# Power_Esc.net
KiCad netlist of a schematic drawn in Altium Designer
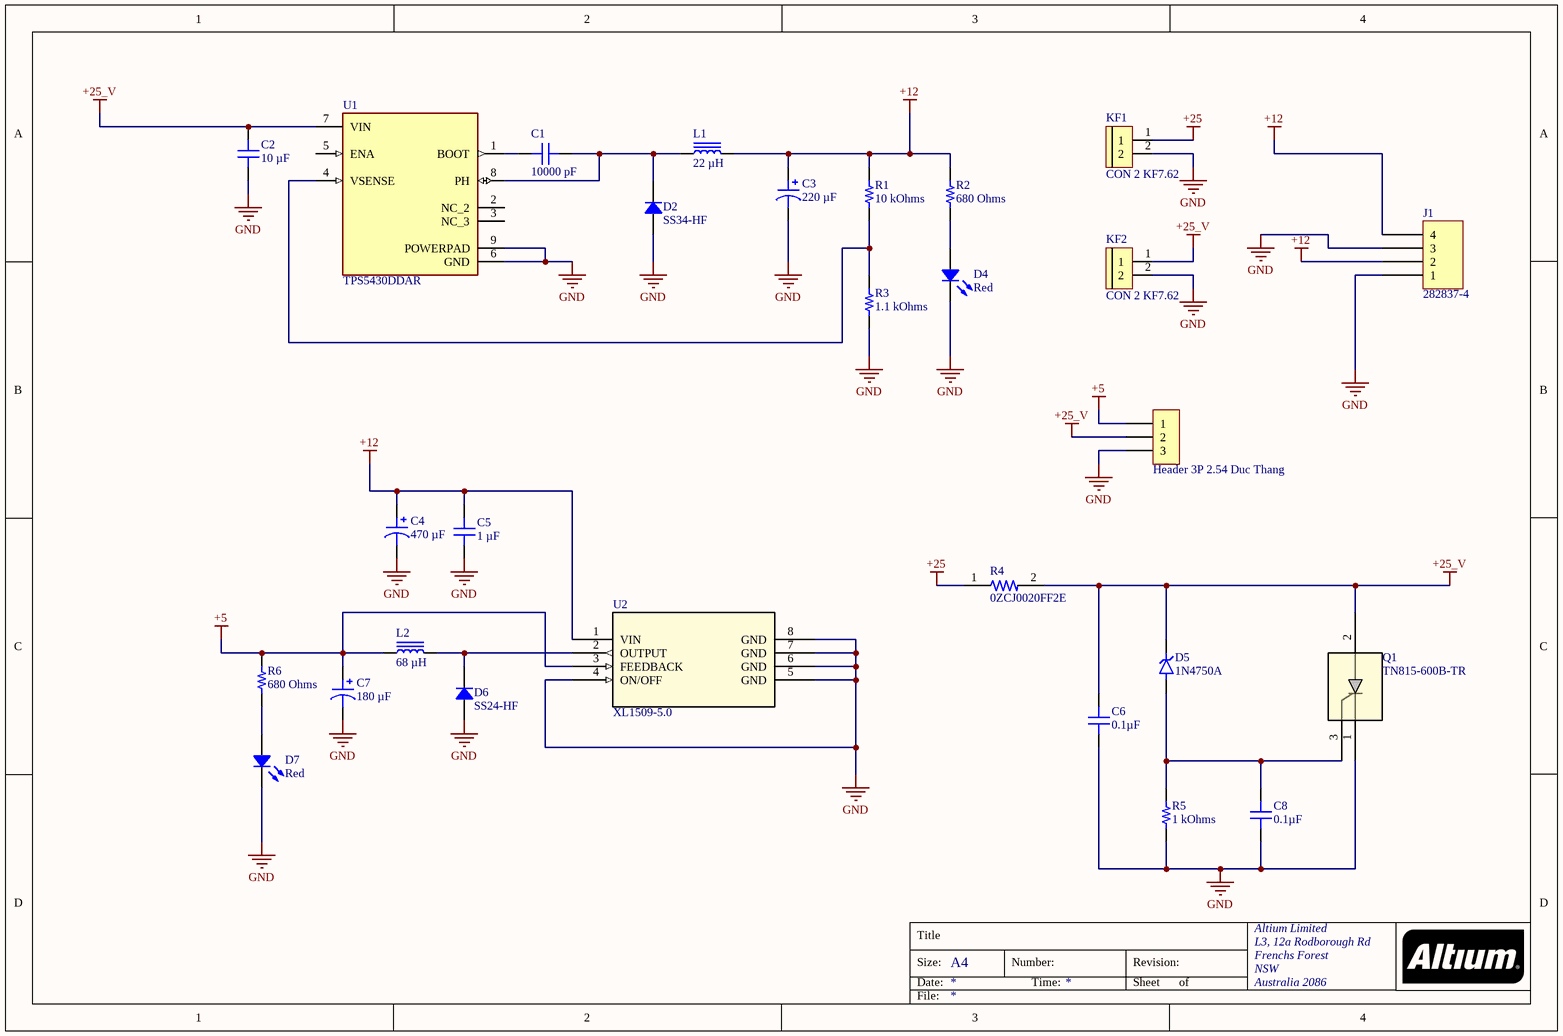
[diagram p0: Power_Esc.SchDoc]

(export (version "E")
  (design (tool "Eeschema 10.0.6"))
  (components
    (comp (ref "C1")
      (value "10000 pF")
      (footprint "CAP 0603_1608")
      (description "CAP CER 0603 10NF 16V X7R 10%")
      (fields (field (name "PART NUMBER") "C0603C103K4REC7867") (field (name "MANUFACTURER") "KEMET"))
      (libsource (lib "Celestial Altium Library - altium_library") (part "Capacitor"))
    )
    (comp (ref "C2")
      (value "10 µF")
      (footprint "CAP 1206_3216 - 0.8MM")
      (description "CAP CER 10UF 50V X5R 1206")
      (fields (field (name "PART NUMBER") "885012108022") (field (name "MANUFACTURER") "Würth Elektronik"))
      (libsource (lib "Celestial Altium Library - altium_library") (part "Capacitor"))
    )
    (comp (ref "C3")
      (value "220 µF")
      (footprint "CAP ALSMD 6.6MM H6.1MM")
      (description "CAP ALUM 220UF 20% 16V SMD")
      (fields
        (field (name "PART NUMBER") "EEE-FT1C221AL")
        (field (name "MANUFACTURER") "Panasonic Electronic Components")
      )
      (libsource (lib "Celestial Altium Library - altium_library") (part "Polarised Capacitor"))
    )
    (comp (ref "C4")
      (value "470 µF")
      (footprint "CAP ALSMD 8.3MM H10.5MM")
      (description "CAP ALUM 470UF 20% 35V SMD")
      (fields
        (field (name "PART NUMBER") "EMZS350ARA471MHA0G")
        (field (name "MANUFACTURER") "United Chemi-Con")
      )
      (libsource (lib "Celestial Altium Library - altium_library") (part "Polarised Capacitor"))
    )
    (comp (ref "C5")
      (value "1 µF")
      (footprint "CAP 0805_2012")
      (description "CAP CER 0805 1UF 16V X7R 5%")
      (fields (field (name "PART NUMBER") "C0805C105J4RECAUTO") (field (name "MANUFACTURER") "KEMET"))
      (libsource (lib "Celestial Altium Library - altium_library") (part "Capacitor"))
    )
    (comp (ref "C6")
      (value "0.1µF")
      (footprint "CAP 0805_2012")
      (description "CAP CER 0.1UF 35V X5R 0805")
      (fields (field (name "PART NUMBER") "0805DD104KAT2A") (field (name "MANUFACTURER") "AVX Corporation"))
      (libsource (lib "Celestial Altium Library - altium_library") (part "Capacitor"))
    )
    (comp (ref "C7")
      (value "180 µF")
      (footprint "CAP ALSMD 6.6MM H8.0MM")
      (description "CAP ALUM 180UF 20% 25V SMD")
      (fields
        (field (name "PART NUMBER") "EEE-FKE181XSP")
        (field (name "MANUFACTURER") "Panasonic Electronic Components")
      )
      (libsource (lib "Celestial Altium Library - altium_library") (part "Polarised Capacitor"))
    )
    (comp (ref "C8")
      (value "0.1µF")
      (footprint "CAP 0805_2012")
      (description "CAP CER 0.1UF 35V X5R 0805")
      (fields (field (name "PART NUMBER") "0805DD104KAT2A") (field (name "MANUFACTURER") "AVX Corporation"))
      (libsource (lib "Celestial Altium Library - altium_library") (part "Capacitor"))
    )
    (comp (ref "D2")
      (value "SS34-HF")
      (footprint "DO214AC SMA")
      (description "DIODE SCHOTTKY 40V 3A DO214AC")
      (fields (field (name "MANUFACTURER") "Comchip Technology"))
      (libsource (lib "Celestial Altium Library - altium_library") (part "Diode"))
    )
    (comp (ref "D4")
      (value "Red")
      (footprint "LED 0805_2012 RED")
      (description "LED RED DIFFUSED 0805 SMD")
      (fields
        (field (name "PART NUMBER") "B1701URO-20D000114U1930")
        (field (name "MANUFACTURER") "Harvatek Corporation")
      )
      (libsource (lib "Celestial Altium Library - altium_library") (part "LED"))
    )
    (comp (ref "D5")
      (value "1N4750A")
      (footprint "DIOAD1060W70L435D230")
      (description "1N4750 Series 1 W 27 V 5 uA Through Hole Zener Diode - DO-41")
      (fields (field (name "MF") "Fairchild Semiconductor"))
      (libsource (lib "1N4750A") (part "1N4750A"))
    )
    (comp (ref "D6")
      (value "SS24-HF")
      (footprint "DO214AC SMA")
      (description "DIODE SCHOTTKY 40V 2A DO214AC")
      (fields (field (name "MANUFACTURER") "Comchip Technology"))
      (libsource (lib "Celestial Altium Library - altium_library") (part "Diode"))
    )
    (comp (ref "D7")
      (value "Red")
      (footprint "LED 0805_2012 RED")
      (description "LED RED DIFFUSED 0805 SMD")
      (fields
        (field (name "PART NUMBER") "B1701URO-20D000114U1930")
        (field (name "MANUFACTURER") "Harvatek Corporation")
      )
      (libsource (lib "Celestial Altium Library - altium_library") (part "LED"))
    )
    (comp (ref "H1")
      (value "Header 3P 2.54 Duc Thang")
      (footprint "XH2.54M-3")
      (description "Cắm")
      (libsource (lib "Header") (part "Header 3P 2.54 Duc Thang"))
    )
    (comp (ref "J1")
      (value "282837-4")
      (footprint "TE 282837-4")
      (description "TERM BLK 4P SIDE ENT 5.08MM PCB")
      (fields (field (name "MANUFACTURER") "TE Connectivity AMP Connectors") (field (name "VOLTAGE") "300 V"))
      (libsource (lib "Celestial Altium Library - altium_library") (part "4 Pin"))
    )
    (comp (ref "KF1")
      (value "CON 2 KF7.62")
      (footprint "CON 2 KF7.62")
      (description "Cắm")
      (libsource (lib "Connector") (part "CON 2 KF7.62"))
    )
    (comp (ref "KF2")
      (value "CON 2 KF7.62")
      (footprint "CON 2 KF7.62")
      (description "Cắm")
      (libsource (lib "Connector") (part "CON 2 KF7.62"))
    )
    (comp (ref "L1")
      (value "22 µH")
      (footprint "WURTH WE-PD 1260")
      (description "FIXED IND 22UH 3.37A 36 MOHM SMD")
      (fields (field (name "PART NUMBER") "744771122") (field (name "MANUFACTURER") "Würth Elektronik"))
      (libsource (lib "Celestial Altium Library - altium_library") (part "Inductor"))
    )
    (comp (ref "L2")
      (value "68 µH")
      (footprint "TDK SLF10145")
      (description "FIXED IND 68UH 1.3A 168 MOHM SMD")
      (fields
        (field (name "PART NUMBER") "SLF10145T-680M1R2-PF")
        (field (name "MANUFACTURER") "TDK Corporation")
      )
      (libsource (lib "Celestial Altium Library - altium_library") (part "Inductor"))
    )
    (comp (ref "Q1")
      (value "TN815-600B-TR")
      (footprint "DPAK228P987X240-3N")
      (description "No Description Available")
      (libsource (lib "TN815-600B-TR") (part "TN815-600B-TR"))
    )
    (comp (ref "R1")
      (value "10 kOhms")
      (footprint "RES 0805_2012")
      (description "RES 10K OHM 5% 1/2W 0805")
      (fields
        (field (name "PART NUMBER") "ERJ-UP6J103V")
        (field (name "MANUFACTURER") "Panasonic Electronic Components")
      )
      (libsource (lib "Celestial Altium Library - altium_library") (part "Resistor"))
    )
    (comp (ref "R2")
      (value "680 Ohms")
      (footprint "RES 0805_2012")
      (description "RES SMD 680 OHM 0.1% 1/8W 0805")
      (fields
        (field (name "PART NUMBER") "ERA-6AEB681V")
        (field (name "MANUFACTURER") "Panasonic Electronic Components")
      )
      (libsource (lib "Celestial Altium Library - altium_library") (part "Resistor"))
    )
    (comp (ref "R3")
      (value "1.1 kOhms")
      (footprint "RES 0805_2012")
      (description "RES SMD 1.1K OHM 0.1% 1/8W 0805")
      (fields
        (field (name "PART NUMBER") "ERA-6APB112V")
        (field (name "MANUFACTURER") "Panasonic Electronic Components")
      )
      (libsource (lib "Celestial Altium Library - altium_library") (part "Resistor"))
    )
    (comp (ref "R4")
      (value "0ZCJ0020FF2E")
      (footprint "RESC3216X125N")
      (description "1206 SMT PPTC ¦ 0.20 Ih ¦ 30V")
      (fields (field (name "MF") "Bel Fuse"))
      (libsource (lib "0ZCJ0020FF2E") (part "0ZCJ0020FF2E"))
    )
    (comp (ref "R5")
      (value "1 kOhms")
      (footprint "RES 0805_2012")
      (description "RES SMD 1K OHM 0.1% 1/10W 0805")
      (fields
        (field (name "PART NUMBER") "CPF0805B1K0E1")
        (field (name "MANUFACTURER") "TE Connectivity Passive Product")
      )
      (libsource (lib "Celestial Altium Library - altium_library") (part "Resistor"))
    )
    (comp (ref "R6")
      (value "680 Ohms")
      (footprint "RES 0805_2012")
      (description "RES SMD 680 OHM 0.1% 1/8W 0805")
      (fields
        (field (name "PART NUMBER") "ERA-6AEB681V")
        (field (name "MANUFACTURER") "Panasonic Electronic Components")
      )
      (libsource (lib "Celestial Altium Library - altium_library") (part "Resistor"))
    )
    (comp (ref "U1")
      (value "TPS5430DDAR")
      (footprint "CONV_TPS5430DDAR")
      (description "5.5V to 36V Input, 3A, 500kHz Step-Down Converter")
      (fields (field (name "MF") "Texas Instruments"))
      (libsource (lib "TPS5430DDAR") (part "TPS5430DDAR"))
    )
    (comp (ref "U2")
      (value "XL1509-5.0")
      (footprint "SOP8SOIC-8_UMW")
      (description "No Description Available")
      (libsource (lib "XL1509-5P0") (part "XL1509-5.0"))
    )
  )
  (nets
    (net (code "1") (name "+5") (class "Default")
      (node (ref "C7") (pin "1") (pinfunction "1_1") (pintype "passive"))
      (node (ref "H1") (pin "1") (pinfunction "1_1") (pintype "passive"))
      (node (ref "L2") (pin "1") (pinfunction "1_1") (pintype "passive"))
      (node (ref "R6") (pin "2") (pinfunction "2_2") (pintype "passive"))
      (node (ref "U2") (pin "3") (pinfunction "FEEDBACK_3") (pintype "input"))
    )
    (net (code "2") (name "+12") (class "Default")
      (node (ref "C3") (pin "1") (pinfunction "1_1") (pintype "passive"))
      (node (ref "C4") (pin "1") (pinfunction "1_1") (pintype "passive"))
      (node (ref "C5") (pin "2") (pinfunction "2_2") (pintype "passive"))
      (node (ref "J1") (pin "2") (pinfunction "2_2") (pintype "passive"))
      (node (ref "J1") (pin "4") (pinfunction "4_4") (pintype "passive"))
      (node (ref "L1") (pin "2") (pinfunction "2_2") (pintype "passive"))
      (node (ref "R1") (pin "2") (pinfunction "2_2") (pintype "passive"))
      (node (ref "R2") (pin "2") (pinfunction "2_2") (pintype "passive"))
      (node (ref "U2") (pin "1") (pinfunction "VIN_1") (pintype "power_in"))
    )
    (net (code "3") (name "+25") (class "Default")
      (node (ref "KF1") (pin "1") (pinfunction "1_1") (pintype "passive"))
      (node (ref "R4") (pin "1") (pinfunction "1_1") (pintype "passive"))
    )
    (net (code "4") (name "+25_V") (class "Default")
      (node (ref "C2") (pin "2") (pinfunction "2_2") (pintype "passive"))
      (node (ref "C6") (pin "2") (pinfunction "2_2") (pintype "passive"))
      (node (ref "D5") (pin "C") (pinfunction "K_C") (pintype "passive"))
      (node (ref "H1") (pin "2") (pinfunction "2_2") (pintype "passive"))
      (node (ref "KF2") (pin "1") (pinfunction "1_1") (pintype "passive"))
      (node (ref "Q1") (pin "2") (pinfunction "2_2") (pintype "passive"))
      (node (ref "R4") (pin "2") (pinfunction "2_2") (pintype "passive"))
      (node (ref "U1") (pin "7") (pinfunction "VIN_7") (pintype "power_in"))
    )
    (net (code "5") (name "GND") (class "Default")
      (node (ref "C2") (pin "1") (pinfunction "1_1") (pintype "passive"))
      (node (ref "C3") (pin "2") (pinfunction "2_2") (pintype "passive"))
      (node (ref "C4") (pin "2") (pinfunction "2_2") (pintype "passive"))
      (node (ref "C5") (pin "1") (pinfunction "1_1") (pintype "passive"))
      (node (ref "C6") (pin "1") (pinfunction "1_1") (pintype "passive"))
      (node (ref "C7") (pin "2") (pinfunction "2_2") (pintype "passive"))
      (node (ref "C8") (pin "1") (pinfunction "1_1") (pintype "passive"))
      (node (ref "D2") (pin "1") (pinfunction "1_1") (pintype "passive"))
      (node (ref "D4") (pin "2") (pinfunction "2_2") (pintype "passive"))
      (node (ref "D6") (pin "1") (pinfunction "1_1") (pintype "passive"))
      (node (ref "D7") (pin "2") (pinfunction "2_2") (pintype "passive"))
      (node (ref "H1") (pin "3") (pinfunction "3_3") (pintype "passive"))
      (node (ref "J1") (pin "1") (pinfunction "1_1") (pintype "passive"))
      (node (ref "J1") (pin "3") (pinfunction "3_3") (pintype "passive"))
      (node (ref "KF1") (pin "2") (pinfunction "2_2") (pintype "passive"))
      (node (ref "KF2") (pin "2") (pinfunction "2_2") (pintype "passive"))
      (node (ref "Q1") (pin "1") (pinfunction "1_1") (pintype "passive"))
      (node (ref "R3") (pin "1") (pinfunction "1_1") (pintype "passive"))
      (node (ref "R5") (pin "1") (pinfunction "1_1") (pintype "passive"))
      (node (ref "U1") (pin "6") (pinfunction "GND_6") (pintype "power_in"))
      (node (ref "U1") (pin "9") (pinfunction "POWERPAD_9") (pintype "power_in"))
      (node (ref "U2") (pin "4") (pinfunction "ON/OFF_4") (pintype "input"))
      (node (ref "U2") (pin "5") (pinfunction "GND_5") (pintype "power_in"))
      (node (ref "U2") (pin "6") (pinfunction "GND_6") (pintype "power_in"))
      (node (ref "U2") (pin "7") (pinfunction "GND_7") (pintype "power_in"))
      (node (ref "U2") (pin "8") (pinfunction "GND_8") (pintype "power_in"))
    )
    (net (code "6") (name "Net-(C8-Pad2)") (class "Default")
      (node (ref "C8") (pin "2") (pinfunction "2_2") (pintype "passive"))
      (node (ref "D5") (pin "A") (pinfunction "A_A") (pintype "passive"))
      (node (ref "Q1") (pin "3") (pinfunction "3_3") (pintype "passive"))
      (node (ref "R5") (pin "2") (pinfunction "2_2") (pintype "passive"))
    )
    (net (code "7") (name "Net-(D4-Pad1)") (class "Default")
      (node (ref "D4") (pin "1") (pinfunction "1_1") (pintype "passive"))
      (node (ref "R2") (pin "1") (pinfunction "1_1") (pintype "passive"))
    )
    (net (code "8") (name "Net-(D7-Pad1)") (class "Default")
      (node (ref "D7") (pin "1") (pinfunction "1_1") (pintype "passive"))
      (node (ref "R6") (pin "1") (pinfunction "1_1") (pintype "passive"))
    )
    (net (code "9") (name "Net-(U1-BOOT)") (class "Default")
      (node (ref "C1") (pin "1") (pinfunction "1_1") (pintype "passive"))
      (node (ref "U1") (pin "1") (pinfunction "BOOT_1") (pintype "output"))
    )
    (net (code "10") (name "Net-(U1-PH)") (class "Default")
      (node (ref "C1") (pin "2") (pinfunction "2_2") (pintype "passive"))
      (node (ref "D2") (pin "2") (pinfunction "2_2") (pintype "passive"))
      (node (ref "L1") (pin "1") (pinfunction "1_1") (pintype "passive"))
      (node (ref "U1") (pin "8") (pinfunction "PH_8") (pintype "bidirectional"))
    )
    (net (code "11") (name "Net-(U1-VSENSE)") (class "Default")
      (node (ref "R1") (pin "1") (pinfunction "1_1") (pintype "passive"))
      (node (ref "R3") (pin "2") (pinfunction "2_2") (pintype "passive"))
      (node (ref "U1") (pin "4") (pinfunction "VSENSE_4") (pintype "input"))
    )
    (net (code "12") (name "Net-(U2-OUTPUT)") (class "Default")
      (node (ref "D6") (pin "2") (pinfunction "2_2") (pintype "passive"))
      (node (ref "L2") (pin "2") (pinfunction "2_2") (pintype "passive"))
      (node (ref "U2") (pin "2") (pinfunction "OUTPUT_2") (pintype "output"))
    )
    (net (code "13") (name "unconnected-(U1-ENA-Pad5)") (class "Default")
      (node (ref "U1") (pin "5") (pinfunction "ENA_5") (pintype "input"))
    )
    (net (code "14") (name "unconnected-(U1-NC_2-Pad2)") (class "Default")
      (node (ref "U1") (pin "2") (pinfunction "NC_2_2") (pintype "passive"))
    )
    (net (code "15") (name "unconnected-(U1-NC_3-Pad3)") (class "Default")
      (node (ref "U1") (pin "3") (pinfunction "NC_3_3") (pintype "passive"))
    )
  )
)
